# TDII_TFT_R00.net
KiCad netlist of a schematic drawn in Altium Designer
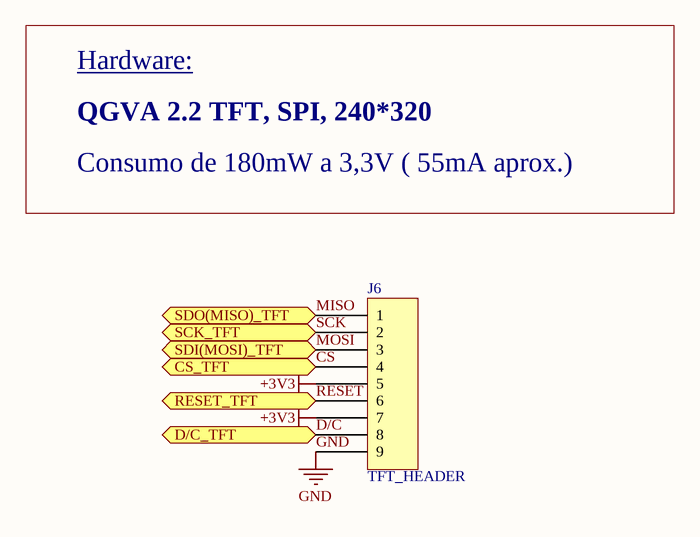
[diagram p0: TDII_TFT_R00.SchDoc]

(export (version "E")
  (design (tool "Eeschema 10.0.6"))
  (components
    (comp (ref "J6")
      (value "TFT_HEADER")
      (footprint "Conector_TFT")
      (libsource (lib "TDII_SCH_LIB_R00") (part "Conector_9 (0.100¨)"))
    )
  )
  (nets
    (net (code "1") (name "+3V3") (class "Default")
      (node (ref "J6") (pin "5") (pinfunction "5_5") (pintype "passive"))
      (node (ref "J6") (pin "7") (pinfunction "7_7") (pintype "passive"))
    )
    (net (code "2") (name "/CS") (class "Default")
      (node (ref "J6") (pin "4") (pinfunction "4_4") (pintype "passive"))
    )
    (net (code "3") (name "/D{slash}C") (class "Default")
      (node (ref "J6") (pin "8") (pinfunction "8_8") (pintype "passive"))
    )
    (net (code "4") (name "/MISO") (class "Default")
      (node (ref "J6") (pin "1") (pinfunction "1_1") (pintype "passive"))
    )
    (net (code "5") (name "/MOSI") (class "Default")
      (node (ref "J6") (pin "3") (pinfunction "3_3") (pintype "passive"))
    )
    (net (code "6") (name "/RESET") (class "Default")
      (node (ref "J6") (pin "6") (pinfunction "6_6") (pintype "passive"))
    )
    (net (code "7") (name "/SCK") (class "Default")
      (node (ref "J6") (pin "2") (pinfunction "2_2") (pintype "passive"))
    )
    (net (code "8") (name "GND") (class "Default")
      (node (ref "J6") (pin "9") (pinfunction "9_9") (pintype "passive"))
    )
  )
)
